# Power.net
KiCad netlist of a schematic drawn in Altium Designer
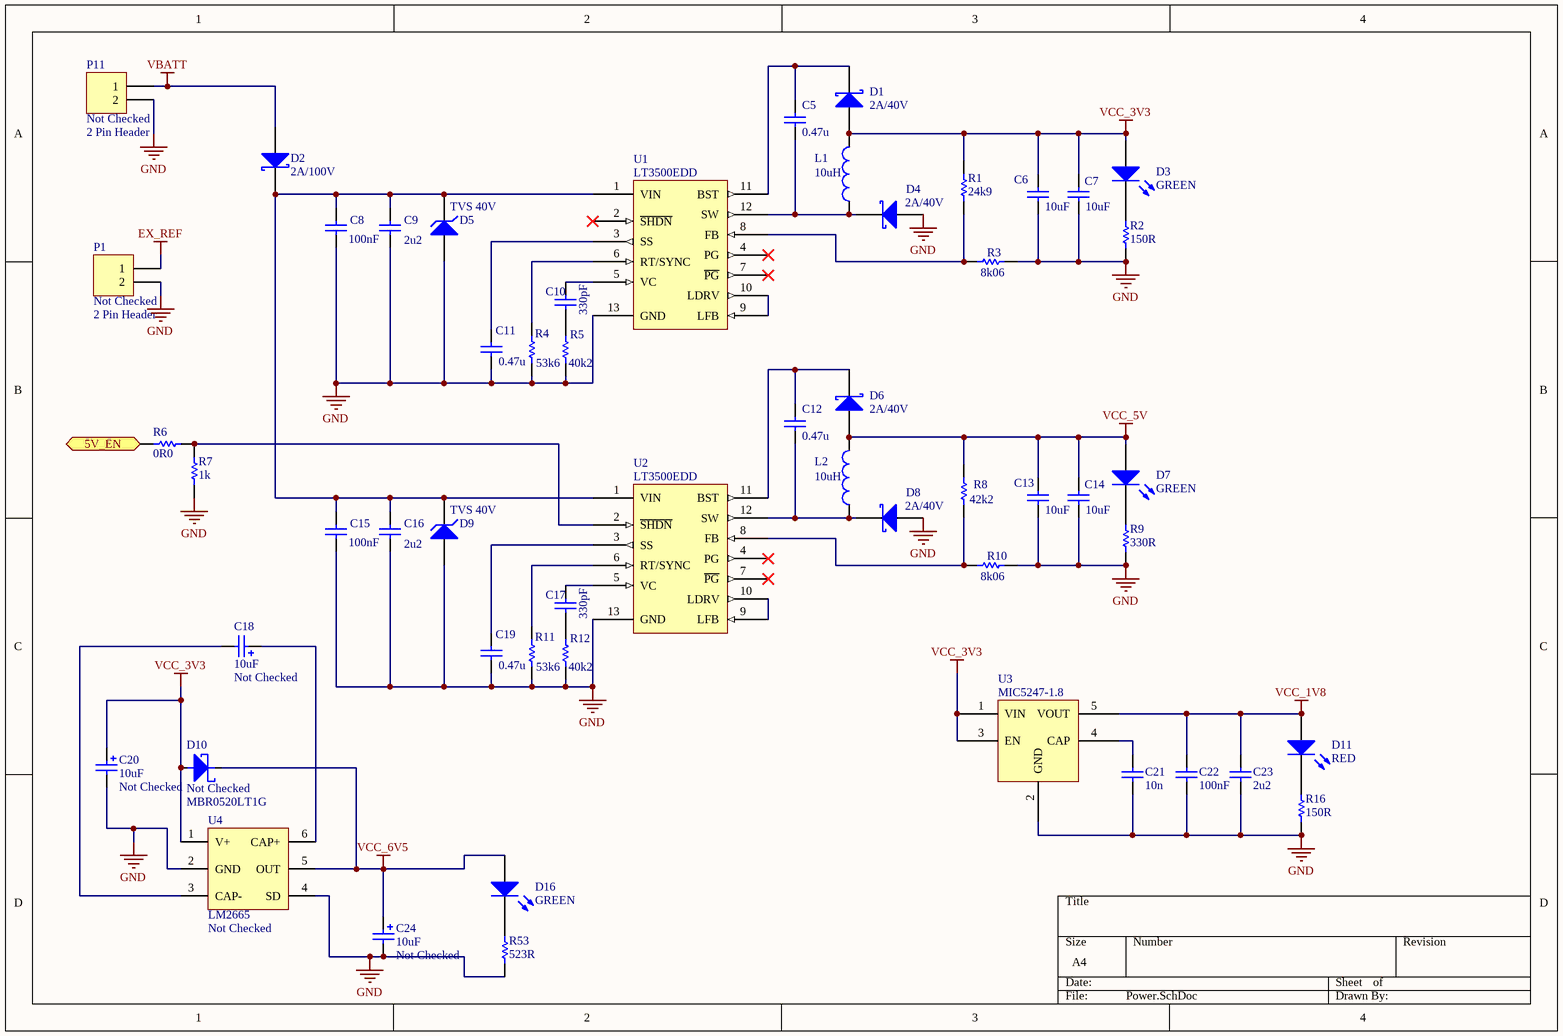
[diagram p0: Power.SchDoc]

(export (version "E")
  (design (tool "Eeschema 10.0.6"))
  (components
    (comp (ref "C5")
      (value "0.47u")
      (footprint "0603")
      (description "CAP CER .47UF 25V X5R 0603")
      (fields
        (field (name "MANUFACTURER") "Taiyo Yuden")
        (field (name "Comment") "CP_470n 0603 25V X5R")
        (field (name "PUBLISHER") "Altium Limited")
      )
      (libsource (lib "GRC sch library") (part "CP_470n 0603 25V X5R"))
    )
    (comp (ref "C6")
      (value "10uF")
      (footprint "GRC PCB library:0805")
      (description "CAP 10uF 10% 10V X5R 0805")
      (fields (field (name "MANUFACTURER") "Murata"))
      (libsource (lib "GRC sch library") (part "CP_10uF 0805"))
    )
    (comp (ref "C7")
      (value "10uF")
      (footprint "GRC PCB library:0805")
      (description "CAP 10uF 10% 10V X5R 0805")
      (fields (field (name "MANUFACTURER") "Murata"))
      (libsource (lib "GRC sch library") (part "CP_10uF 0805"))
    )
    (comp (ref "C8")
      (value "100nF")
      (footprint "GRC PCB library:0603")
      (description "CAP CER .10UF 50V X5R 0603")
      (fields (field (name "MANUFACTURER") "Taiyo Yuden"))
      (libsource (lib "GRC sch library") (part "CP_100nF 0603"))
    )
    (comp (ref "C9")
      (value "2u2")
      (footprint "GRC PCB library:1206")
      (description "CAP CER 2u2 50V Y5V 1206")
      (fields (field (name "MANUFACTURER") "Taiyo Yuden") (field (name "Comment") "CP_2u2 1206"))
      (libsource (lib "GRC sch library") (part "CP_2u2 1206"))
    )
    (comp (ref "C10")
      (value "330pF")
      (footprint "GRC PCB library:0603")
      (description "CAP 330PF 50V CERAMIC X7R 0603")
      (fields (field (name "MANUFACTURER") "Yageo") (field (name "Comment") "CP_330pF 0603"))
      (libsource (lib "GRC sch library") (part "CP_330pF 0603"))
    )
    (comp (ref "C11")
      (value "0.47u")
      (footprint "0603")
      (description "CAP CER .47UF 25V X5R 0603")
      (fields
        (field (name "MANUFACTURER") "Taiyo Yuden")
        (field (name "Comment") "CP_470n 0603 25V X5R")
        (field (name "PUBLISHER") "Altium Limited")
      )
      (libsource (lib "GRC sch library") (part "CP_470n 0603 25V X5R"))
    )
    (comp (ref "C12")
      (value "0.47u")
      (footprint "0603")
      (description "CAP CER .47UF 25V X5R 0603")
      (fields
        (field (name "MANUFACTURER") "Taiyo Yuden")
        (field (name "Comment") "CP_470n 0603 25V X5R")
        (field (name "PUBLISHER") "Altium Limited")
      )
      (libsource (lib "GRC sch library") (part "CP_470n 0603 25V X5R"))
    )
    (comp (ref "C13")
      (value "10uF")
      (footprint "GRC PCB library:0805")
      (description "CAP 10uF 10% 10V X5R 0805")
      (fields (field (name "MANUFACTURER") "Murata"))
      (libsource (lib "GRC sch library") (part "CP_10uF 0805"))
    )
    (comp (ref "C14")
      (value "10uF")
      (footprint "GRC PCB library:0805")
      (description "CAP 10uF 10% 10V X5R 0805")
      (fields (field (name "MANUFACTURER") "Murata"))
      (libsource (lib "GRC sch library") (part "CP_10uF 0805"))
    )
    (comp (ref "C15")
      (value "100nF")
      (footprint "GRC PCB library:0603")
      (description "CAP CER .10UF 50V X5R 0603")
      (fields (field (name "MANUFACTURER") "Taiyo Yuden"))
      (libsource (lib "GRC sch library") (part "CP_100nF 0603"))
    )
    (comp (ref "C16")
      (value "2u2")
      (footprint "GRC PCB library:1206")
      (description "CAP CER 2u2 50V Y5V 1206")
      (fields (field (name "MANUFACTURER") "Taiyo Yuden") (field (name "Comment") "CP_2u2 1206"))
      (libsource (lib "GRC sch library") (part "CP_2u2 1206"))
    )
    (comp (ref "C17")
      (value "330pF")
      (footprint "GRC PCB library:0603")
      (description "CAP 330PF 50V CERAMIC X7R 0603")
      (fields (field (name "MANUFACTURER") "Yageo") (field (name "Comment") "CP_330pF 0603"))
      (libsource (lib "GRC sch library") (part "CP_330pF 0603"))
    )
    (comp (ref "C18")
      (value "10uF")
      (footprint "1206P")
      (description "CAP 10uF 20% 10V 300mOhm 1206")
      (fields (field (name "MANUFACTURER") "AVX") (field (name "VERIFY") "Not Checked"))
      (libsource (lib "GRC sch library") (part "CP_TANT_10uF_1206"))
    )
    (comp (ref "C19")
      (value "0.47u")
      (footprint "0603")
      (description "CAP CER .47UF 25V X5R 0603")
      (fields
        (field (name "MANUFACTURER") "Taiyo Yuden")
        (field (name "Comment") "CP_470n 0603 25V X5R")
        (field (name "PUBLISHER") "Altium Limited")
      )
      (libsource (lib "GRC sch library") (part "CP_470n 0603 25V X5R"))
    )
    (comp (ref "C20")
      (value "10uF")
      (footprint "1206P")
      (description "CAP 10uF 20% 10V 300mOhm 1206")
      (fields (field (name "MANUFACTURER") "AVX") (field (name "VERIFY") "Not Checked"))
      (libsource (lib "GRC sch library") (part "CP_TANT_10uF_1206"))
    )
    (comp (ref "C21")
      (value "10n")
      (footprint "GRC PCB library:0603")
      (description "CAP CER .10UF 50V X5R 0603")
      (fields (field (name "MANUFACTURER") "Taiyo Yuden"))
      (libsource (lib "GRC sch library") (part "CP_100nF 0603"))
    )
    (comp (ref "C22")
      (value "100nF")
      (footprint "GRC PCB library:0603")
      (description "CAP CER .10UF 50V X5R 0603")
      (fields (field (name "MANUFACTURER") "Taiyo Yuden"))
      (libsource (lib "GRC sch library") (part "CP_100nF 0603"))
    )
    (comp (ref "C23")
      (value "2u2")
      (footprint "GRC PCB library:1206")
      (description "CAP CER 2u2 50V Y5V 1206")
      (fields (field (name "MANUFACTURER") "Taiyo Yuden") (field (name "Comment") "CP_2u2_50V_1206"))
      (libsource (lib "GRC sch library") (part "CP_2u2_50V_1206"))
    )
    (comp (ref "C24")
      (value "10uF")
      (footprint "1206P")
      (description "CAP 10uF 20% 10V 300mOhm 1206")
      (fields (field (name "MANUFACTURER") "AVX") (field (name "VERIFY") "Not Checked"))
      (libsource (lib "GRC sch library") (part "CP_TANT_10uF_1206"))
    )
    (comp (ref "D1")
      (value "2A/40V")
      (footprint "GRC PCB library:SMA_DIODE")
      (description "Schottky Diode - 2A/40V")
      (fields (field (name "MANUFACTURER") "Diodes Inc"))
      (libsource (lib "GRC sch library") (part "DS_B240A-13-F"))
    )
    (comp (ref "D2")
      (value "2A/100V")
      (footprint "GRC PCB library:SMB_DIODE")
      (description "Schottky Diode - 2A/100V")
      (fields (field (name "MANUFACTURER") "Vishay/General Semiconductor"))
      (libsource (lib "GRC sch library") (part "DS_SS2H10-E3/52T"))
    )
    (comp (ref "D3")
      (value "GREEN")
      (footprint "Diode_0805")
      (description "Green LED 0805")
      (fields (field (name "Comment") "LED Green"))
      (libsource (lib "GRC sch library") (part "DL_LED Green 0805"))
    )
    (comp (ref "D4")
      (value "2A/40V")
      (footprint "GRC PCB library:SMA_DIODE")
      (description "Schottky Diode - 2A/40V")
      (fields (field (name "MANUFACTURER") "Diodes Inc"))
      (libsource (lib "GRC sch library") (part "DS_B240A-13-F"))
    )
    (comp (ref "D5")
      (value "TVS 40V")
      (footprint "GRC PCB library:SMB_DIODE")
      (description "DIODE TVS 40V 600W UNIDIR  SMB")
      (fields (field (name "MANUFACTURER") "LittelFuse"))
      (libsource (lib "GRC sch library") (part "DZ_40v TVS"))
    )
    (comp (ref "D6")
      (value "2A/40V")
      (footprint "GRC PCB library:SMA_DIODE")
      (description "Schottky Diode - 2A/40V")
      (fields (field (name "MANUFACTURER") "Diodes Inc"))
      (libsource (lib "GRC sch library") (part "DS_B240A-13-F"))
    )
    (comp (ref "D7")
      (value "GREEN")
      (footprint "Diode_0805")
      (description "Green LED 0805")
      (fields (field (name "Comment") "LED Green"))
      (libsource (lib "GRC sch library") (part "DL_LED Green 0805"))
    )
    (comp (ref "D8")
      (value "2A/40V")
      (footprint "GRC PCB library:SMA_DIODE")
      (description "Schottky Diode - 2A/40V")
      (fields (field (name "MANUFACTURER") "Diodes Inc"))
      (libsource (lib "GRC sch library") (part "DS_B240A-13-F"))
    )
    (comp (ref "D9")
      (value "TVS 40V")
      (footprint "GRC PCB library:SMB_DIODE")
      (description "DIODE TVS 40V 600W UNIDIR  SMB")
      (fields (field (name "MANUFACTURER") "LittelFuse"))
      (libsource (lib "GRC sch library") (part "DZ_40v TVS"))
    )
    (comp (ref "D10")
      (value "MBR0520LT1G")
      (footprint "SOD123")
      (description "DIODE SCHOTTKY 20V 0.5A SOD123")
      (fields (field (name "MANUFACTURER") "ON Semiconductor") (field (name "VERIFY") "Not Checked"))
      (libsource (lib "GRC sch library") (part "DS_MBR0520LT1G"))
    )
    (comp (ref "D11")
      (value "RED")
      (footprint "Diode_0805")
      (description "Red LED 1.7V 0805")
      (fields (field (name "MANUFACTURER") "CML") (field (name "Comment") "LED Red"))
      (libsource (lib "GRC sch library") (part "DL_LED 1.7V Red 0805"))
    )
    (comp (ref "D16")
      (value "GREEN")
      (footprint "Diode_0805")
      (description "Green LED 0805")
      (fields (field (name "Comment") "LED Green"))
      (libsource (lib "GRC sch library") (part "DL_LED Green 0805"))
    )
    (comp (ref "L1")
      (value "10uH")
      (footprint "GRC PCB library:WE-PD")
      (description "INDUCTOR POWER 10UH 2.0A SMD")
      (fields (field (name "MANUFACTURER") "Wurth Electronics Inc"))
      (libsource (lib "GRC sch library") (part "IN_10uH 2A SMT"))
    )
    (comp (ref "L2")
      (value "10uH")
      (footprint "GRC PCB library:WE-PD")
      (description "INDUCTOR POWER 10UH 2.0A SMD")
      (fields (field (name "MANUFACTURER") "Wurth Electronics Inc"))
      (libsource (lib "GRC sch library") (part "IN_10uH 2A SMT"))
    )
    (comp (ref "P1")
      (value "2 Pin Header")
      (footprint "CONN_2X1_SMT_RA_1.25MM")
      (description "CONN HDR VERT 2POS .100\" SNGL")
      (fields (field (name "MANUFACTURER") "Molex") (field (name "VERIFY") "Not Checked"))
      (libsource (lib "checked") (part "JP_2PIN HDR_SMT_RA_MOLEX"))
    )
    (comp (ref "P11")
      (value "2 Pin Header")
      (footprint "POWER_PADS")
      (fields (field (name "VERIFY") "Not Checked"))
      (libsource (lib "checked") (part "JP_2PIN HDR_SMT_RA_MOLEX"))
    )
    (comp (ref "R1")
      (value "24k9")
      (footprint "GRC PCB library:0603")
      (description "RES 24.9K OHM 1/10W 1% 0603 SMD")
      (fields (field (name "MANUFACTURER") "ROHM"))
      (libsource (lib "GRC sch library") (part "RS_24k9 0603"))
    )
    (comp (ref "R2")
      (value "150R")
      (footprint "GRC PCB library:0603")
      (description "RES 150 OHM 1/10W 1% 0603 SMD")
      (fields (field (name "MANUFACTURER") "ROHM"))
      (libsource (lib "GRC sch library") (part "RS_150R 0603"))
    )
    (comp (ref "R3")
      (value "8k06")
      (footprint "GRC PCB library:0603")
      (description "RES 8k06 OHM 1/10W 1% 0603 SMD")
      (fields (field (name "MANUFACTURER") "ROHM"))
      (libsource (lib "GRC sch library") (part "RS_8k06 0603"))
    )
    (comp (ref "R4")
      (value "53k6")
      (footprint "GRC PCB library:0603")
      (description "RES 53.6K OHM 1/10W 1% 0603 SMD")
      (fields (field (name "MANUFACTURER") "ROHM"))
      (libsource (lib "GRC sch library") (part "RS_53k6 0603"))
    )
    (comp (ref "R5")
      (value "40k2")
      (footprint "GRC PCB library:0603")
      (description "RES 40.2K OHM 1/10W 1% 0603 SMD")
      (fields (field (name "MANUFACTURER") "ROHM"))
      (libsource (lib "GRC sch library") (part "RS_40k2 0603"))
    )
    (comp (ref "R6")
      (value "0R0")
      (footprint "GRC PCB library:0603")
      (description "RES 0.0 OHM 1/10W 5% 0603 SMD")
      (fields (field (name "MANUFACTURER") "Rohm"))
      (libsource (lib "GRC sch library") (part "RS_0R0 0603"))
    )
    (comp (ref "R7")
      (value "1k")
      (footprint "GRC PCB library:0603")
      (description "RES 1.00K OHM 1/10W 1% 0603 SMD")
      (fields (field (name "MANUFACTURER") "ROHM"))
      (libsource (lib "GRC sch library") (part "RS_1k 0603"))
    )
    (comp (ref "R8")
      (value "42k2")
      (footprint "GRC PCB library:0603")
      (description "RES 42.2K OHM 1/10W 1% 0603 SMD")
      (fields (field (name "MANUFACTURER") "ROHM"))
      (libsource (lib "GRC sch library") (part "RS_42k2 0603"))
    )
    (comp (ref "R9")
      (value "330R")
      (footprint "GRC PCB library:0603")
      (description "RES 330 OHM 1/10W 1% 0603 SMD")
      (fields (field (name "MANUFACTURER") "Yageo"))
      (libsource (lib "GRC sch library") (part "RS_330R 0603"))
    )
    (comp (ref "R10")
      (value "8k06")
      (footprint "GRC PCB library:0603")
      (description "RES 8k06 OHM 1/10W 1% 0603 SMD")
      (fields (field (name "MANUFACTURER") "ROHM"))
      (libsource (lib "GRC sch library") (part "RS_8k06 0603"))
    )
    (comp (ref "R11")
      (value "53k6")
      (footprint "GRC PCB library:0603")
      (description "RES 53.6K OHM 1/10W 1% 0603 SMD")
      (fields (field (name "MANUFACTURER") "ROHM"))
      (libsource (lib "GRC sch library") (part "RS_53k6 0603"))
    )
    (comp (ref "R12")
      (value "40k2")
      (footprint "GRC PCB library:0603")
      (description "RES 40.2K OHM 1/10W 1% 0603 SMD")
      (fields (field (name "MANUFACTURER") "ROHM"))
      (libsource (lib "GRC sch library") (part "RS_40k2 0603"))
    )
    (comp (ref "R16")
      (value "150R")
      (footprint "GRC PCB library:0603")
      (description "RES 100K OHM 1/10W 1% 0603 SMD")
      (fields (field (name "MANUFACTURER") "Yageo"))
      (libsource (lib "GRC sch library") (part "RS_100k 0603"))
    )
    (comp (ref "R53")
      (value "523R")
      (footprint "GRC PCB library:0603")
      (description "RES 523 OHM 1/10W 1% 0603 SMD")
      (fields (field (name "MANUFACTURER") "Yageo"))
      (libsource (lib "GRC sch library") (part "RS_523R 0603"))
    )
    (comp (ref "U1")
      (value "LT3500EDD")
      (footprint "12-DFN")
      (description "IC REG STP-DWN 2A 12-DFN")
      (fields
        (field (name "MANUFACTURER") "Linear Technology")
        (field (name "Comment") "IC_LT3500EDD")
        (field (name "PUBLISHER") "Altium Limited")
      )
      (libsource (lib "GRC sch library") (part "IC_LT3500EDD"))
    )
    (comp (ref "U2")
      (value "LT3500EDD")
      (footprint "12-DFN")
      (description "IC REG STP-DWN 2A 12-DFN")
      (fields
        (field (name "MANUFACTURER") "Linear Technology")
        (field (name "Comment") "IC_LT3500EDD")
        (field (name "PUBLISHER") "Altium Limited")
      )
      (libsource (lib "GRC sch library") (part "IC_LT3500EDD"))
    )
    (comp (ref "U3")
      (value "MIC5247-1.8")
      (footprint "SOT23-5")
      (description "1.8V linear regulator")
      (fields (field (name "MANUFACTURER") "Micrel"))
      (libsource (lib "GRC sch library") (part "IC_MIC5247-1.8YM5"))
    )
    (comp (ref "U4")
      (value "LM2665")
      (footprint "SOT23-6")
      (description "Switched Capacitor Voltage Converter")
      (fields (field (name "MANUFACTURER") "National Semiconductor") (field (name "VERIFY") "Not Checked"))
      (libsource (lib "checked") (part "IC_LM2665"))
    )
  )
  (nets
    (net (code "1") (name "/5V_EN") (class "Default")
      (node (ref "R6") (pin "2") (pinfunction "2_2") (pintype "passive"))
    )
    (net (code "2") (name "EX_REF") (class "Default")
      (node (ref "P1") (pin "1") (pinfunction "1_1") (pintype "passive"))
    )
    (net (code "3") (name "GND") (class "Default")
      (node (ref "C11") (pin "2") (pinfunction "2_2") (pintype "passive"))
      (node (ref "C13") (pin "2") (pinfunction "2_2") (pintype "passive"))
      (node (ref "C14") (pin "2") (pinfunction "2_2") (pintype "passive"))
      (node (ref "C15") (pin "1") (pinfunction "1_1") (pintype "passive"))
      (node (ref "C16") (pin "2") (pinfunction "2_2") (pintype "passive"))
      (node (ref "C19") (pin "2") (pinfunction "2_2") (pintype "passive"))
      (node (ref "C20") (pin "2") (pinfunction "2_2") (pintype "passive"))
      (node (ref "C21") (pin "1") (pinfunction "1_1") (pintype "passive"))
      (node (ref "C22") (pin "1") (pinfunction "1_1") (pintype "passive"))
      (node (ref "C23") (pin "1") (pinfunction "1_1") (pintype "passive"))
      (node (ref "C24") (pin "2") (pinfunction "2_2") (pintype "passive"))
      (node (ref "C6") (pin "2") (pinfunction "2_2") (pintype "passive"))
      (node (ref "C7") (pin "2") (pinfunction "2_2") (pintype "passive"))
      (node (ref "C8") (pin "1") (pinfunction "1_1") (pintype "passive"))
      (node (ref "C9") (pin "2") (pinfunction "2_2") (pintype "passive"))
      (node (ref "D4") (pin "1") (pinfunction "A_1") (pintype "passive"))
      (node (ref "D5") (pin "1") (pinfunction "A_1") (pintype "passive"))
      (node (ref "D8") (pin "1") (pinfunction "A_1") (pintype "passive"))
      (node (ref "D9") (pin "1") (pinfunction "A_1") (pintype "passive"))
      (node (ref "P1") (pin "2") (pinfunction "2_2") (pintype "passive"))
      (node (ref "P11") (pin "2") (pinfunction "2_2") (pintype "passive"))
      (node (ref "R10") (pin "1") (pinfunction "1_1") (pintype "passive"))
      (node (ref "R11") (pin "1") (pinfunction "1_1") (pintype "passive"))
      (node (ref "R12") (pin "1") (pinfunction "1_1") (pintype "passive"))
      (node (ref "R16") (pin "1") (pinfunction "1_1") (pintype "passive"))
      (node (ref "R2") (pin "1") (pinfunction "1_1") (pintype "passive"))
      (node (ref "R3") (pin "1") (pinfunction "1_1") (pintype "passive"))
      (node (ref "R4") (pin "1") (pinfunction "1_1") (pintype "passive"))
      (node (ref "R5") (pin "1") (pinfunction "1_1") (pintype "passive"))
      (node (ref "R53") (pin "2") (pinfunction "2_2") (pintype "passive"))
      (node (ref "R7") (pin "1") (pinfunction "1_1") (pintype "passive"))
      (node (ref "R9") (pin "1") (pinfunction "1_1") (pintype "passive"))
      (node (ref "U1") (pin "13") (pinfunction "GND_13") (pintype "power_in"))
      (node (ref "U2") (pin "13") (pinfunction "GND_13") (pintype "power_in"))
      (node (ref "U3") (pin "2") (pinfunction "GND_2") (pintype "power_in"))
      (node (ref "U4") (pin "2") (pinfunction "GND_2") (pintype "passive"))
      (node (ref "U4") (pin "4") (pinfunction "SD_4") (pintype "passive"))
    )
    (net (code "4") (name "Net-(C10-Pad2)") (class "Default")
      (node (ref "C10") (pin "2") (pinfunction "2_2") (pintype "passive"))
      (node (ref "R5") (pin "2") (pinfunction "2_2") (pintype "passive"))
    )
    (net (code "5") (name "Net-(C17-Pad2)") (class "Default")
      (node (ref "C17") (pin "2") (pinfunction "2_2") (pintype "passive"))
      (node (ref "R12") (pin "2") (pinfunction "2_2") (pintype "passive"))
    )
    (net (code "6") (name "Net-(D1-K)") (class "Default")
      (node (ref "C5") (pin "2") (pinfunction "2_2") (pintype "passive"))
      (node (ref "D1") (pin "2") (pinfunction "K_2") (pintype "passive"))
      (node (ref "U1") (pin "11") (pinfunction "BST_11") (pintype "output"))
    )
    (net (code "7") (name "Net-(D2-K)") (class "Default")
      (node (ref "C15") (pin "2") (pinfunction "2_2") (pintype "passive"))
      (node (ref "C16") (pin "1") (pinfunction "1_1") (pintype "passive"))
      (node (ref "C8") (pin "2") (pinfunction "2_2") (pintype "passive"))
      (node (ref "C9") (pin "1") (pinfunction "1_1") (pintype "passive"))
      (node (ref "D2") (pin "2") (pinfunction "K_2") (pintype "passive"))
      (node (ref "D5") (pin "2") (pinfunction "K_2") (pintype "passive"))
      (node (ref "D9") (pin "2") (pinfunction "K_2") (pintype "passive"))
      (node (ref "U1") (pin "1") (pinfunction "VIN_1") (pintype "power_in"))
      (node (ref "U2") (pin "1") (pinfunction "VIN_1") (pintype "power_in"))
    )
    (net (code "8") (name "Net-(D3-K)") (class "Default")
      (node (ref "D3") (pin "2") (pinfunction "K_2") (pintype "passive"))
      (node (ref "R2") (pin "2") (pinfunction "2_2") (pintype "passive"))
    )
    (net (code "9") (name "Net-(D4-K)") (class "Default")
      (node (ref "C5") (pin "1") (pinfunction "1_1") (pintype "passive"))
      (node (ref "D4") (pin "2") (pinfunction "K_2") (pintype "passive"))
      (node (ref "L1") (pin "1") (pinfunction "1_1") (pintype "passive"))
      (node (ref "U1") (pin "12") (pinfunction "SW_12") (pintype "output"))
    )
    (net (code "10") (name "Net-(D6-K)") (class "Default")
      (node (ref "C12") (pin "2") (pinfunction "2_2") (pintype "passive"))
      (node (ref "D6") (pin "2") (pinfunction "K_2") (pintype "passive"))
      (node (ref "U2") (pin "11") (pinfunction "BST_11") (pintype "output"))
    )
    (net (code "11") (name "Net-(D7-K)") (class "Default")
      (node (ref "D7") (pin "2") (pinfunction "K_2") (pintype "passive"))
      (node (ref "R9") (pin "2") (pinfunction "2_2") (pintype "passive"))
    )
    (net (code "12") (name "Net-(D8-K)") (class "Default")
      (node (ref "C12") (pin "1") (pinfunction "1_1") (pintype "passive"))
      (node (ref "D8") (pin "2") (pinfunction "K_2") (pintype "passive"))
      (node (ref "L2") (pin "1") (pinfunction "1_1") (pintype "passive"))
      (node (ref "U2") (pin "12") (pinfunction "SW_12") (pintype "output"))
    )
    (net (code "13") (name "Net-(D11-K)") (class "Default")
      (node (ref "D11") (pin "2") (pinfunction "K_2") (pintype "passive"))
      (node (ref "R16") (pin "2") (pinfunction "2_2") (pintype "passive"))
    )
    (net (code "14") (name "Net-(D16-K)") (class "Default")
      (node (ref "D16") (pin "2") (pinfunction "K_2") (pintype "passive"))
      (node (ref "R53") (pin "1") (pinfunction "1_1") (pintype "passive"))
    )
    (net (code "15") (name "Net-(U1-FB)") (class "Default")
      (node (ref "R1") (pin "1") (pinfunction "1_1") (pintype "passive"))
      (node (ref "R3") (pin "2") (pinfunction "2_2") (pintype "passive"))
      (node (ref "U1") (pin "8") (pinfunction "FB_8") (pintype "input"))
    )
    (net (code "16") (name "Net-(U1-LDRV)") (class "Default")
      (node (ref "U1") (pin "10") (pinfunction "LDRV_10") (pintype "output"))
      (node (ref "U1") (pin "9") (pinfunction "LFB_9") (pintype "input"))
    )
    (net (code "17") (name "Net-(U1-RT{slash}SYNC)") (class "Default")
      (node (ref "R4") (pin "2") (pinfunction "2_2") (pintype "passive"))
      (node (ref "U1") (pin "6") (pinfunction "RT/SYNC_6") (pintype "input"))
    )
    (net (code "18") (name "Net-(U1-SS)") (class "Default")
      (node (ref "C11") (pin "1") (pinfunction "1_1") (pintype "passive"))
      (node (ref "U1") (pin "3") (pinfunction "SS_3") (pintype "output"))
    )
    (net (code "19") (name "Net-(U1-VC)") (class "Default")
      (node (ref "C10") (pin "1") (pinfunction "1_1") (pintype "passive"))
      (node (ref "U1") (pin "5") (pinfunction "VC_5") (pintype "input"))
    )
    (net (code "20") (name "Net-(U2-FB)") (class "Default")
      (node (ref "R10") (pin "2") (pinfunction "2_2") (pintype "passive"))
      (node (ref "R8") (pin "1") (pinfunction "1_1") (pintype "passive"))
      (node (ref "U2") (pin "8") (pinfunction "FB_8") (pintype "input"))
    )
    (net (code "21") (name "Net-(U2-LDRV)") (class "Default")
      (node (ref "U2") (pin "10") (pinfunction "LDRV_10") (pintype "output"))
      (node (ref "U2") (pin "9") (pinfunction "LFB_9") (pintype "input"))
    )
    (net (code "22") (name "Net-(U2-RT{slash}SYNC)") (class "Default")
      (node (ref "R11") (pin "2") (pinfunction "2_2") (pintype "passive"))
      (node (ref "U2") (pin "6") (pinfunction "RT/SYNC_6") (pintype "input"))
    )
    (net (code "23") (name "Net-(U2-SS)") (class "Default")
      (node (ref "C19") (pin "1") (pinfunction "1_1") (pintype "passive"))
      (node (ref "U2") (pin "3") (pinfunction "SS_3") (pintype "output"))
    )
    (net (code "24") (name "Net-(U2-VC)") (class "Default")
      (node (ref "C17") (pin "1") (pinfunction "1_1") (pintype "passive"))
      (node (ref "U2") (pin "5") (pinfunction "VC_5") (pintype "input"))
    )
    (net (code "25") (name "Net-(U2-~{SHDN})") (class "Default")
      (node (ref "R6") (pin "1") (pinfunction "1_1") (pintype "passive"))
      (node (ref "R7") (pin "2") (pinfunction "2_2") (pintype "passive"))
      (node (ref "U2") (pin "2") (pinfunction "~{SHDN}_2") (pintype "input"))
    )
    (net (code "26") (name "Net-(U3-CAP)") (class "Default")
      (node (ref "C21") (pin "2") (pinfunction "2_2") (pintype "passive"))
      (node (ref "U3") (pin "4") (pinfunction "CAP_4") (pintype "power_in"))
    )
    (net (code "27") (name "Net-(U4-CAP+)") (class "Default")
      (node (ref "C18") (pin "1") (pinfunction "1_1") (pintype "passive"))
      (node (ref "U4") (pin "6") (pinfunction "CAP+_6") (pintype "power_in"))
    )
    (net (code "28") (name "Net-(U4-CAP-)") (class "Default")
      (node (ref "C18") (pin "2") (pinfunction "2_2") (pintype "passive"))
      (node (ref "U4") (pin "3") (pinfunction "CAP-_3") (pintype "passive"))
    )
    (net (code "29") (name "VBATT") (class "Default")
      (node (ref "D2") (pin "1") (pinfunction "A_1") (pintype "passive"))
      (node (ref "P11") (pin "1") (pinfunction "1_1") (pintype "passive"))
    )
    (net (code "30") (name "VCC_1V8") (class "Default")
      (node (ref "C22") (pin "2") (pinfunction "2_2") (pintype "passive"))
      (node (ref "C23") (pin "2") (pinfunction "2_2") (pintype "passive"))
      (node (ref "D11") (pin "1") (pinfunction "A_1") (pintype "passive"))
      (node (ref "U3") (pin "5") (pinfunction "VOUT_5") (pintype "power_in"))
    )
    (net (code "31") (name "VCC_3V3") (class "Default")
      (node (ref "C20") (pin "1") (pinfunction "1_1") (pintype "passive"))
      (node (ref "C6") (pin "1") (pinfunction "1_1") (pintype "passive"))
      (node (ref "C7") (pin "1") (pinfunction "1_1") (pintype "passive"))
      (node (ref "D1") (pin "1") (pinfunction "A_1") (pintype "passive"))
      (node (ref "D10") (pin "1") (pinfunction "A_1") (pintype "passive"))
      (node (ref "D3") (pin "1") (pinfunction "A_1") (pintype "passive"))
      (node (ref "L1") (pin "2") (pinfunction "2_2") (pintype "passive"))
      (node (ref "R1") (pin "2") (pinfunction "2_2") (pintype "passive"))
      (node (ref "U3") (pin "1") (pinfunction "VIN_1") (pintype "power_in"))
      (node (ref "U3") (pin "3") (pinfunction "EN_3") (pintype "power_in"))
      (node (ref "U4") (pin "1") (pinfunction "V+_1") (pintype "power_in"))
    )
    (net (code "32") (name "VCC_5V") (class "Default")
      (node (ref "C13") (pin "1") (pinfunction "1_1") (pintype "passive"))
      (node (ref "C14") (pin "1") (pinfunction "1_1") (pintype "passive"))
      (node (ref "D6") (pin "1") (pinfunction "A_1") (pintype "passive"))
      (node (ref "D7") (pin "1") (pinfunction "A_1") (pintype "passive"))
      (node (ref "L2") (pin "2") (pinfunction "2_2") (pintype "passive"))
      (node (ref "R8") (pin "2") (pinfunction "2_2") (pintype "passive"))
    )
    (net (code "33") (name "VCC_6V5") (class "Default")
      (node (ref "C24") (pin "1") (pinfunction "1_1") (pintype "passive"))
      (node (ref "D10") (pin "2") (pinfunction "K_2") (pintype "passive"))
      (node (ref "D16") (pin "1") (pinfunction "A_1") (pintype "passive"))
      (node (ref "U4") (pin "5") (pinfunction "OUT_5") (pintype "power_in"))
    )
    (net (code "34") (name "unconnected-(U1-PG-Pad4)") (class "Default")
      (node (ref "U1") (pin "4") (pinfunction "PG_4") (pintype "output+no_connect"))
    )
    (net (code "35") (name "unconnected-(U1-~{PG}-Pad7)") (class "Default")
      (node (ref "U1") (pin "7") (pinfunction "~{PG}_7") (pintype "output+no_connect"))
    )
    (net (code "36") (name "unconnected-(U1-~{SHDN}-Pad2)") (class "Default")
      (node (ref "U1") (pin "2") (pinfunction "~{SHDN}_2") (pintype "input+no_connect"))
    )
    (net (code "37") (name "unconnected-(U2-PG-Pad4)") (class "Default")
      (node (ref "U2") (pin "4") (pinfunction "PG_4") (pintype "output+no_connect"))
    )
    (net (code "38") (name "unconnected-(U2-~{PG}-Pad7)") (class "Default")
      (node (ref "U2") (pin "7") (pinfunction "~{PG}_7") (pintype "output+no_connect"))
    )
  )
)
